# KC_Input_VAS_Schematic.net
KiCad netlist of a schematic drawn in Altium Designer
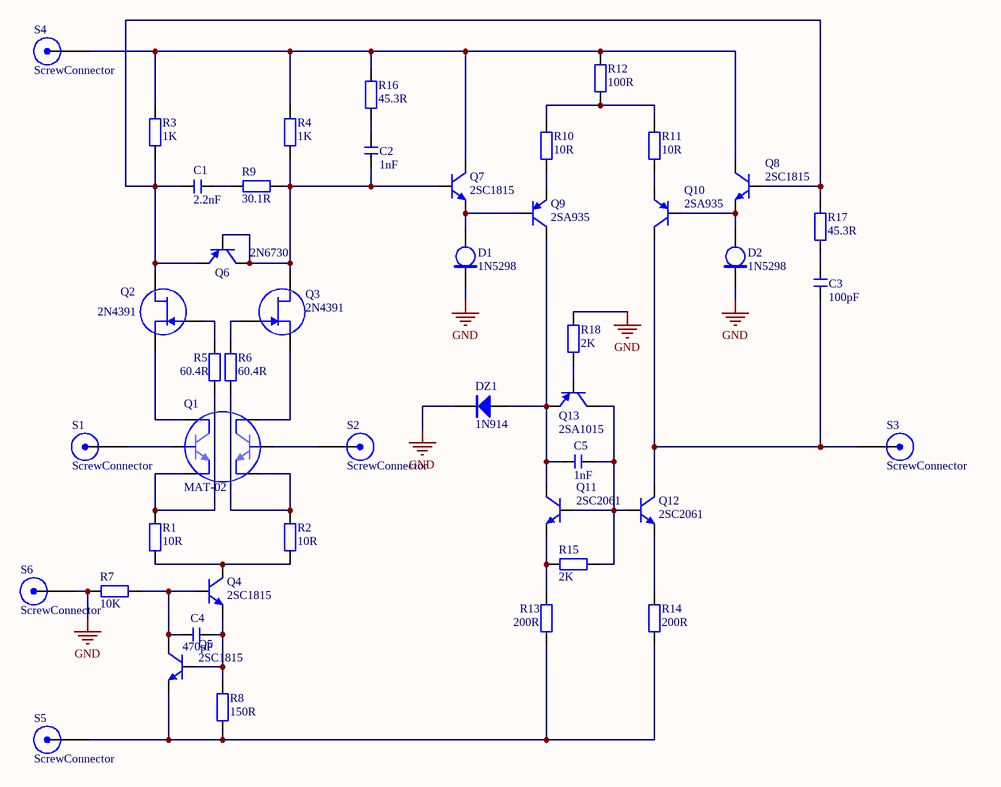
[diagram p0: KC_Input_VAS_Schematic.SchDoc]

(export (version "E")
  (design (tool "Eeschema 10.0.6"))
  (components
    (comp (ref "C1")
      (value "2.2nF")
      (footprint "CBB 6.3*6.3*5")
      (description "CBB电容")
      (fields (field (name "版权归属") "源创客"))
      (libsource (lib "电阻-电容-电感") (part "C-CBB"))
    )
    (comp (ref "C2")
      (value "1nF")
      (footprint "CBB 6.3*6.3*5")
      (description "CBB电容")
      (fields (field (name "版权归属") "源创客"))
      (libsource (lib "电阻-电容-电感") (part "C-CBB"))
    )
    (comp (ref "C3")
      (value "100pF")
      (footprint "CBB 6.3*6.3*5")
      (description "CBB电容")
      (fields (field (name "版权归属") "源创客"))
      (libsource (lib "电阻-电容-电感") (part "C-CBB"))
    )
    (comp (ref "C4")
      (value "470pF")
      (footprint "CBB 6.3*6.3*5")
      (description "CBB电容")
      (fields (field (name "版权归属") "源创客"))
      (libsource (lib "电阻-电容-电感") (part "C-CBB"))
    )
    (comp (ref "C5")
      (value "1nF")
      (footprint "CBB 6.3*6.3*5")
      (description "CBB电容")
      (fields (field (name "版权归属") "源创客"))
      (libsource (lib "电阻-电容-电感") (part "C-CBB"))
    )
    (comp (ref "D1")
      (value "1N5298")
      (footprint "DO-41G")
      (description "Current Regulator Diodes")
      (libsource (lib "二极管-整流桥") (part "1N5xxx"))
    )
    (comp (ref "D2")
      (value "1N5298")
      (footprint "DO-41G")
      (description "Current Regulator Diodes")
      (libsource (lib "二极管-整流桥") (part "1N5xxx"))
    )
    (comp (ref "DZ1")
      (value "1N914")
      (footprint "DO-41G")
      (description "高速开关管 1V/0.25W")
      (libsource (lib "二极管-整流桥") (part "1N914"))
    )
    (comp (ref "Q1")
      (value "MAT-02")
      (footprint "TO78_SMALLHOLE")
      (description "孪生对管-NPN型 40V/20ma")
      (libsource (lib "三极管") (part "MAT-02"))
    )
    (comp (ref "Q2")
      (value "2N4391")
      (footprint "TO-18_SMALLHOLE")
      (description "N沟道JFET开关管 40V/150ma")
      (libsource (lib "场效应管") (part "2N4391"))
    )
    (comp (ref "Q3")
      (value "2N4391")
      (footprint "TO-18_SMALLHOLE")
      (description "N沟道JFET开关管 40V/150ma")
      (libsource (lib "场效应管") (part "2N4391"))
    )
    (comp (ref "Q4")
      (value "2SC1815")
      (footprint "TO92A")
      (description "音频放大-NPN型")
      (libsource (lib "三极管") (part "2SC1815"))
    )
    (comp (ref "Q5")
      (value "2SC1815")
      (footprint "TO92A")
      (description "音频放大-NPN型")
      (libsource (lib "三极管") (part "2SC1815"))
    )
    (comp (ref "Q6")
      (value "2N6730")
      (footprint "TO92A_SmallHole")
      (description "中功率放大-PNP型")
      (libsource (lib "三极管") (part "2N6728/6729/6730"))
    )
    (comp (ref "Q7")
      (value "2SC1815")
      (footprint "TO92A")
      (description "音频放大-NPN型")
      (libsource (lib "三极管") (part "2SC1815"))
    )
    (comp (ref "Q8")
      (value "2SC1815")
      (footprint "TO92A")
      (description "音频放大-NPN型")
      (libsource (lib "三极管") (part "2SC1815"))
    )
    (comp (ref "Q9")
      (value "2SA935")
      (footprint "TO92A_SmallHole")
      (description "音频功放-PNP型 50V/500ma")
      (libsource (lib "三极管") (part "2SA935"))
    )
    (comp (ref "Q10")
      (value "2SA935")
      (footprint "TO92A_SmallHole")
      (description "音频功放-PNP型 50V/500ma")
      (libsource (lib "三极管") (part "2SA935"))
    )
    (comp (ref "Q11")
      (value "2SC2061")
      (footprint "TO92A_SmallHole")
      (description "音频放大-NPN型 50V/500ma")
      (libsource (lib "三极管") (part "2SC2061"))
    )
    (comp (ref "Q12")
      (value "2SC2061")
      (footprint "TO92A_SmallHole")
      (description "音频放大-NPN型 50V/500ma")
      (libsource (lib "三极管") (part "2SC2061"))
    )
    (comp (ref "Q13")
      (value "2SA1015")
      (footprint "TO92A_SmallHole")
      (description "音频放大-PNP型")
      (libsource (lib "三极管") (part "2SA1015"))
    )
    (comp (ref "R1")
      (value "10R")
      (footprint "RS 1/4W")
      (description "直插色环电阻")
      (fields (field (name "版权归属") "源创客"))
      (libsource (lib "电阻-电容-电感") (part "R-CRR"))
    )
    (comp (ref "R2")
      (value "10R")
      (footprint "RS 1/4W")
      (description "直插色环电阻")
      (fields (field (name "版权归属") "源创客"))
      (libsource (lib "电阻-电容-电感") (part "R-CRR"))
    )
    (comp (ref "R3")
      (value "1K")
      (footprint "RS 1/4W")
      (description "直插色环电阻")
      (fields (field (name "版权归属") "源创客"))
      (libsource (lib "电阻-电容-电感") (part "R-CRR"))
    )
    (comp (ref "R4")
      (value "1K")
      (footprint "RS 1/4W")
      (description "直插色环电阻")
      (fields (field (name "版权归属") "源创客"))
      (libsource (lib "电阻-电容-电感") (part "R-CRR"))
    )
    (comp (ref "R5")
      (value "60.4R")
      (footprint "RS 1/4W")
      (description "直插色环电阻")
      (fields (field (name "版权归属") "源创客"))
      (libsource (lib "电阻-电容-电感") (part "R-CRR"))
    )
    (comp (ref "R6")
      (value "60.4R")
      (footprint "RS 1/4W")
      (description "直插色环电阻")
      (fields (field (name "版权归属") "源创客"))
      (libsource (lib "电阻-电容-电感") (part "R-CRR"))
    )
    (comp (ref "R7")
      (value "10K")
      (footprint "RS 1/4W")
      (description "直插色环电阻")
      (fields (field (name "版权归属") "源创客"))
      (libsource (lib "电阻-电容-电感") (part "R-CRR"))
    )
    (comp (ref "R8")
      (value "150R")
      (footprint "RS 1/4W")
      (description "直插色环电阻")
      (fields (field (name "版权归属") "源创客"))
      (libsource (lib "电阻-电容-电感") (part "R-CRR"))
    )
    (comp (ref "R9")
      (value "30.1R")
      (footprint "RS 1/4W")
      (description "直插色环电阻")
      (fields (field (name "版权归属") "源创客"))
      (libsource (lib "电阻-电容-电感") (part "R-CRR"))
    )
    (comp (ref "R10")
      (value "10R")
      (footprint "RS 1/4W")
      (description "直插色环电阻")
      (fields (field (name "版权归属") "源创客"))
      (libsource (lib "电阻-电容-电感") (part "R-CRR"))
    )
    (comp (ref "R11")
      (value "10R")
      (footprint "RS 1/4W")
      (description "直插色环电阻")
      (fields (field (name "版权归属") "源创客"))
      (libsource (lib "电阻-电容-电感") (part "R-CRR"))
    )
    (comp (ref "R12")
      (value "100R")
      (footprint "RS 1/4W")
      (description "直插色环电阻")
      (fields (field (name "版权归属") "源创客"))
      (libsource (lib "电阻-电容-电感") (part "R-CRR"))
    )
    (comp (ref "R13")
      (value "200R")
      (footprint "RS 1/4W")
      (description "直插色环电阻")
      (fields (field (name "版权归属") "源创客"))
      (libsource (lib "电阻-电容-电感") (part "R-CRR"))
    )
    (comp (ref "R14")
      (value "200R")
      (footprint "RS 1/4W")
      (description "直插色环电阻")
      (fields (field (name "版权归属") "源创客"))
      (libsource (lib "电阻-电容-电感") (part "R-CRR"))
    )
    (comp (ref "R15")
      (value "2K")
      (footprint "RS 1/4W")
      (description "直插色环电阻")
      (fields (field (name "版权归属") "源创客"))
      (libsource (lib "电阻-电容-电感") (part "R-CRR"))
    )
    (comp (ref "R16")
      (value "45.3R")
      (footprint "RS 1/4W")
      (description "直插色环电阻")
      (fields (field (name "版权归属") "源创客"))
      (libsource (lib "电阻-电容-电感") (part "R-CRR"))
    )
    (comp (ref "R17")
      (value "45.3R")
      (footprint "RS 1/4W")
      (description "直插色环电阻")
      (fields (field (name "版权归属") "源创客"))
      (libsource (lib "电阻-电容-电感") (part "R-CRR"))
    )
    (comp (ref "R18")
      (value "2K")
      (footprint "RS 1/4W")
      (description "直插色环电阻")
      (fields (field (name "版权归属") "源创客"))
      (libsource (lib "电阻-电容-电感") (part "R-CRR"))
    )
    (comp (ref "S1")
      (value "ScrewConnector")
      (footprint "Screw-M2-s")
      (description "Screw Connector")
      (libsource (lib "Connectors") (part "ScrewConnector"))
    )
    (comp (ref "S2")
      (value "ScrewConnector")
      (footprint "Screw-M2-s")
      (description "Screw Connector")
      (libsource (lib "Connectors") (part "ScrewConnector"))
    )
    (comp (ref "S3")
      (value "ScrewConnector")
      (footprint "Screw-M2-s")
      (description "Screw Connector")
      (libsource (lib "Connectors") (part "ScrewConnector"))
    )
    (comp (ref "S4")
      (value "ScrewConnector")
      (footprint "Screw-M2-s")
      (description "Screw Connector")
      (libsource (lib "Connectors") (part "ScrewConnector"))
    )
    (comp (ref "S5")
      (value "ScrewConnector")
      (footprint "Screw-M2-s")
      (description "Screw Connector")
      (libsource (lib "Connectors") (part "ScrewConnector"))
    )
    (comp (ref "S6")
      (value "ScrewConnector")
      (footprint "Screw-M2-s")
      (description "Screw Connector")
      (libsource (lib "Connectors") (part "ScrewConnector"))
    )
  )
  (nets
    (net (code "1") (name "GND") (class "Default")
      (node (ref "D1") (pin "1") (pinfunction "Cathode_1") (pintype "passive"))
      (node (ref "D2") (pin "1") (pinfunction "Cathode_1") (pintype "passive"))
      (node (ref "DZ1") (pin "2") (pinfunction "K_2") (pintype "passive"))
      (node (ref "R18") (pin "2") (pinfunction "2_2") (pintype "passive"))
      (node (ref "R7") (pin "1") (pinfunction "1_1") (pintype "passive"))
      (node (ref "S6") (pin "1") (pinfunction "X_1") (pintype "passive"))
    )
    (net (code "2") (name "Net-(C1-Pad2)") (class "Default")
      (node (ref "C1") (pin "2") (pinfunction "2_2") (pintype "passive"))
      (node (ref "R9") (pin "1") (pinfunction "1_1") (pintype "passive"))
    )
    (net (code "3") (name "Net-(C2-Pad1)") (class "Default")
      (node (ref "C2") (pin "1") (pinfunction "1_1") (pintype "passive"))
      (node (ref "R16") (pin "1") (pinfunction "1_1") (pintype "passive"))
    )
    (net (code "4") (name "Net-(C3-Pad2)") (class "Default")
      (node (ref "C3") (pin "2") (pinfunction "2_2") (pintype "passive"))
      (node (ref "R17") (pin "1") (pinfunction "1_1") (pintype "passive"))
    )
    (net (code "5") (name "Net-(D1-Anode)") (class "Default")
      (node (ref "D1") (pin "2") (pinfunction "Anode_2") (pintype "passive"))
      (node (ref "Q7") (pin "1") (pinfunction "E_1") (pintype "passive"))
      (node (ref "Q9") (pin "3") (pinfunction "B_3") (pintype "passive"))
    )
    (net (code "6") (name "Net-(D2-Anode)") (class "Default")
      (node (ref "D2") (pin "2") (pinfunction "Anode_2") (pintype "passive"))
      (node (ref "Q10") (pin "3") (pinfunction "B_3") (pintype "passive"))
      (node (ref "Q8") (pin "1") (pinfunction "E_1") (pintype "passive"))
    )
    (net (code "7") (name "Net-(DZ1-A)") (class "Default")
      (node (ref "C5") (pin "1") (pinfunction "1_1") (pintype "passive"))
      (node (ref "DZ1") (pin "1") (pinfunction "A_1") (pintype "passive"))
      (node (ref "Q11") (pin "2") (pinfunction "C_2") (pintype "passive"))
      (node (ref "Q13") (pin "1") (pinfunction "E_1") (pintype "passive"))
      (node (ref "Q9") (pin "2") (pinfunction "C_2") (pintype "passive"))
    )
    (net (code "8") (name "Net-(Q1-E-Pad3)") (class "Default")
      (node (ref "Q1") (pin "3") (pinfunction "E_3") (pintype "passive"))
      (node (ref "R1") (pin "2") (pinfunction "2_2") (pintype "passive"))
      (node (ref "R5") (pin "1") (pinfunction "1_1") (pintype "passive"))
    )
    (net (code "9") (name "Net-(Q1-E-Pad5)") (class "Default")
      (node (ref "Q1") (pin "5") (pinfunction "E_5") (pintype "passive"))
      (node (ref "R2") (pin "2") (pinfunction "2_2") (pintype "passive"))
      (node (ref "R6") (pin "1") (pinfunction "1_1") (pintype "passive"))
    )
    (net (code "10") (name "Net-(Q2-D)") (class "Default")
      (node (ref "C1") (pin "1") (pinfunction "1_1") (pintype "passive"))
      (node (ref "Q2") (pin "3") (pinfunction "D_3") (pintype "passive"))
      (node (ref "Q6") (pin "1") (pinfunction "E_1") (pintype "passive"))
      (node (ref "Q8") (pin "3") (pinfunction "B_3") (pintype "passive"))
      (node (ref "R17") (pin "2") (pinfunction "2_2") (pintype "passive"))
      (node (ref "R3") (pin "1") (pinfunction "1_1") (pintype "passive"))
    )
    (net (code "11") (name "Net-(Q2-G)") (class "Default")
      (node (ref "Q2") (pin "2") (pinfunction "G_2") (pintype "passive"))
      (node (ref "R5") (pin "2") (pinfunction "2_2") (pintype "passive"))
    )
    (net (code "12") (name "Net-(Q2-S)") (class "Default")
      (node (ref "Q1") (pin "1") (pinfunction "C_1") (pintype "passive"))
      (node (ref "Q2") (pin "1") (pinfunction "S_1") (pintype "passive"))
    )
    (net (code "13") (name "Net-(Q3-D)") (class "Default")
      (node (ref "C2") (pin "2") (pinfunction "2_2") (pintype "passive"))
      (node (ref "Q3") (pin "3") (pinfunction "D_3") (pintype "passive"))
      (node (ref "Q6") (pin "2") (pinfunction "C_2") (pintype "passive"))
      (node (ref "Q6") (pin "3") (pinfunction "B_3") (pintype "passive"))
      (node (ref "Q7") (pin "3") (pinfunction "B_3") (pintype "passive"))
      (node (ref "R4") (pin "1") (pinfunction "1_1") (pintype "passive"))
      (node (ref "R9") (pin "2") (pinfunction "2_2") (pintype "passive"))
    )
    (net (code "14") (name "Net-(Q3-G)") (class "Default")
      (node (ref "Q3") (pin "2") (pinfunction "G_2") (pintype "passive"))
      (node (ref "R6") (pin "2") (pinfunction "2_2") (pintype "passive"))
    )
    (net (code "15") (name "Net-(Q3-S)") (class "Default")
      (node (ref "Q1") (pin "7") (pinfunction "C_7") (pintype "passive"))
      (node (ref "Q3") (pin "1") (pinfunction "S_1") (pintype "passive"))
    )
    (net (code "16") (name "Net-(Q4-B)") (class "Default")
      (node (ref "C4") (pin "1") (pinfunction "1_1") (pintype "passive"))
      (node (ref "Q4") (pin "3") (pinfunction "B_3") (pintype "passive"))
      (node (ref "Q5") (pin "2") (pinfunction "C_2") (pintype "passive"))
      (node (ref "R7") (pin "2") (pinfunction "2_2") (pintype "passive"))
    )
    (net (code "17") (name "Net-(Q4-C)") (class "Default")
      (node (ref "Q4") (pin "2") (pinfunction "C_2") (pintype "passive"))
      (node (ref "R1") (pin "1") (pinfunction "1_1") (pintype "passive"))
      (node (ref "R2") (pin "1") (pinfunction "1_1") (pintype "passive"))
    )
    (net (code "18") (name "Net-(Q4-E)") (class "Default")
      (node (ref "C4") (pin "2") (pinfunction "2_2") (pintype "passive"))
      (node (ref "Q4") (pin "1") (pinfunction "E_1") (pintype "passive"))
      (node (ref "Q5") (pin "3") (pinfunction "B_3") (pintype "passive"))
      (node (ref "R8") (pin "1") (pinfunction "1_1") (pintype "passive"))
    )
    (net (code "19") (name "Net-(Q5-E)") (class "Default")
      (node (ref "Q5") (pin "1") (pinfunction "E_1") (pintype "passive"))
      (node (ref "R13") (pin "1") (pinfunction "1_1") (pintype "passive"))
      (node (ref "R14") (pin "1") (pinfunction "1_1") (pintype "passive"))
      (node (ref "R8") (pin "2") (pinfunction "2_2") (pintype "passive"))
      (node (ref "S5") (pin "1") (pinfunction "X_1") (pintype "passive"))
    )
    (net (code "20") (name "Net-(Q7-C)") (class "Default")
      (node (ref "Q7") (pin "2") (pinfunction "C_2") (pintype "passive"))
      (node (ref "Q8") (pin "2") (pinfunction "C_2") (pintype "passive"))
      (node (ref "R12") (pin "2") (pinfunction "2_2") (pintype "passive"))
      (node (ref "R16") (pin "2") (pinfunction "2_2") (pintype "passive"))
      (node (ref "R3") (pin "2") (pinfunction "2_2") (pintype "passive"))
      (node (ref "R4") (pin "2") (pinfunction "2_2") (pintype "passive"))
      (node (ref "S4") (pin "1") (pinfunction "X_1") (pintype "passive"))
    )
    (net (code "21") (name "Net-(Q9-E)") (class "Default")
      (node (ref "Q9") (pin "1") (pinfunction "E_1") (pintype "passive"))
      (node (ref "R10") (pin "1") (pinfunction "1_1") (pintype "passive"))
    )
    (net (code "22") (name "Net-(Q10-C)") (class "Default")
      (node (ref "C3") (pin "1") (pinfunction "1_1") (pintype "passive"))
      (node (ref "Q10") (pin "2") (pinfunction "C_2") (pintype "passive"))
      (node (ref "Q12") (pin "2") (pinfunction "C_2") (pintype "passive"))
      (node (ref "S3") (pin "1") (pinfunction "X_1") (pintype "passive"))
    )
    (net (code "23") (name "Net-(Q10-E)") (class "Default")
      (node (ref "Q10") (pin "1") (pinfunction "E_1") (pintype "passive"))
      (node (ref "R11") (pin "1") (pinfunction "1_1") (pintype "passive"))
    )
    (net (code "24") (name "Net-(Q11-B)") (class "Default")
      (node (ref "C5") (pin "2") (pinfunction "2_2") (pintype "passive"))
      (node (ref "Q11") (pin "3") (pinfunction "B_3") (pintype "passive"))
      (node (ref "Q12") (pin "3") (pinfunction "B_3") (pintype "passive"))
      (node (ref "Q13") (pin "2") (pinfunction "C_2") (pintype "passive"))
      (node (ref "R15") (pin "1") (pinfunction "1_1") (pintype "passive"))
    )
    (net (code "25") (name "Net-(Q11-E)") (class "Default")
      (node (ref "Q11") (pin "1") (pinfunction "E_1") (pintype "passive"))
      (node (ref "R13") (pin "2") (pinfunction "2_2") (pintype "passive"))
      (node (ref "R15") (pin "2") (pinfunction "2_2") (pintype "passive"))
    )
    (net (code "26") (name "Net-(Q12-E)") (class "Default")
      (node (ref "Q12") (pin "1") (pinfunction "E_1") (pintype "passive"))
      (node (ref "R14") (pin "2") (pinfunction "2_2") (pintype "passive"))
    )
    (net (code "27") (name "Net-(Q13-B)") (class "Default")
      (node (ref "Q13") (pin "3") (pinfunction "B_3") (pintype "passive"))
      (node (ref "R18") (pin "1") (pinfunction "1_1") (pintype "passive"))
    )
    (net (code "28") (name "Net-(R10-Pad2)") (class "Default")
      (node (ref "R10") (pin "2") (pinfunction "2_2") (pintype "passive"))
      (node (ref "R11") (pin "2") (pinfunction "2_2") (pintype "passive"))
      (node (ref "R12") (pin "1") (pinfunction "1_1") (pintype "passive"))
    )
    (net (code "29") (name "Net-(S1-X)") (class "Default")
      (node (ref "Q1") (pin "2") (pinfunction "B_2") (pintype "passive"))
      (node (ref "S1") (pin "1") (pinfunction "X_1") (pintype "passive"))
    )
    (net (code "30") (name "Net-(S2-X)") (class "Default")
      (node (ref "Q1") (pin "6") (pinfunction "B_6") (pintype "passive"))
      (node (ref "S2") (pin "1") (pinfunction "X_1") (pintype "passive"))
    )
  )
)
